# Filters_PWM60Hz.net
KiCad netlist of a schematic drawn in Altium Designer
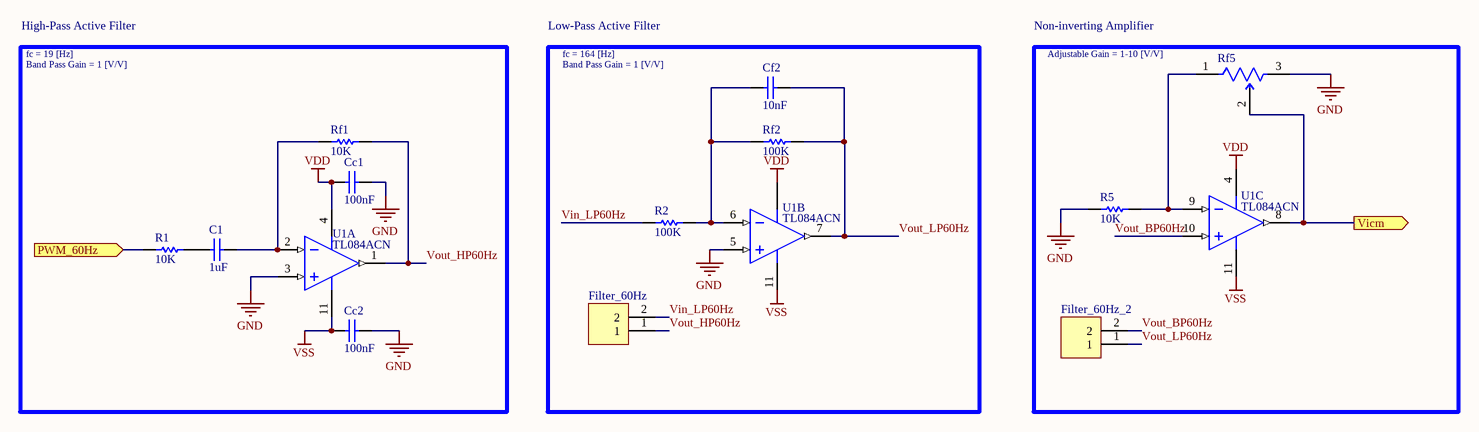
[diagram p0: Filters_PWM60Hz.SchDoc]

(export (version "E")
  (design (tool "Eeschema 10.0.6"))
  (components
    (comp (ref "C1")
      (value "1uF")
      (footprint "condensateur 0.1uf 100mil")
      (description "Capacitor")
      (fields (field (name "Comment") "Cap") (field (name "PUBLISHER") "Altium Limited"))
      (libsource (lib "signal-generator") (part "Cap"))
    )
    (comp (ref "Cc1")
      (value "100nF")
      (footprint "condensateur 0.1uf 100mil")
      (description "Capacitor")
      (fields (field (name "Comment") "Cap") (field (name "PUBLISHER") "Altium Limited"))
      (libsource (lib "signal-generator") (part "Cap"))
    )
    (comp (ref "Cc2")
      (value "100nF")
      (footprint "condensateur 0.1uf 100mil")
      (description "Capacitor")
      (fields (field (name "Comment") "Cap") (field (name "PUBLISHER") "Altium Limited"))
      (libsource (lib "signal-generator") (part "Cap"))
    )
    (comp (ref "Cf2")
      (value "10nF")
      (footprint "condensateur 0.1uf 100mil")
      (description "Capacitor")
      (fields (field (name "Comment") "Cap") (field (name "PUBLISHER") "Altium Limited"))
      (libsource (lib "signal-generator") (part "Cap"))
    )
    (comp (ref "Filter_60Hz")
      (value "Jumper")
      (footprint "Header 2P 100mil")
      (description "CONN HEADER VERT 3POS 2.54MM")
      (fields (field (name "PUBLISHER") "Altium Limited"))
      (libsource (lib "PCB_Alimentation_équipe1") (part "header 2 pin_UL"))
    )
    (comp (ref "Filter_60Hz_2")
      (value "Jumper")
      (footprint "Header 2P 100mil")
      (description "CONN HEADER VERT 3POS 2.54MM")
      (fields (field (name "PUBLISHER") "Altium Limited"))
      (libsource (lib "PCB_Alimentation_équipe1") (part "header 2 pin_UL"))
    )
    (comp (ref "R1")
      (value "10K")
      (footprint "Resistor_Axial 0.4")
      (description "Resistor")
      (fields (field (name "Comment") "Res1") (field (name "PUBLISHER") "Altium Limited"))
      (libsource (lib "signal-generator") (part "Res1"))
    )
    (comp (ref "R2")
      (value "100K")
      (footprint "Resistor_Axial 0.4")
      (description "Resistor")
      (fields (field (name "Comment") "Res1") (field (name "PUBLISHER") "Altium Limited"))
      (libsource (lib "signal-generator") (part "Res1"))
    )
    (comp (ref "R5")
      (value "10K")
      (footprint "Resistor_Axial 0.4")
      (description "Resistor")
      (fields (field (name "Comment") "Res1") (field (name "PUBLISHER") "Altium Limited"))
      (libsource (lib "signal-generator") (part "Res1"))
    )
    (comp (ref "Rf1")
      (value "10K")
      (footprint "Resistor_Axial 0.4")
      (description "Resistor")
      (fields (field (name "Comment") "Res1") (field (name "PUBLISHER") "Altium Limited"))
      (libsource (lib "signal-generator") (part "Res1"))
    )
    (comp (ref "Rf2")
      (value "100K")
      (footprint "Resistor_Axial 0.4")
      (description "Resistor")
      (fields (field (name "Comment") "Res1") (field (name "PUBLISHER") "Altium Limited"))
      (libsource (lib "signal-generator") (part "Res1"))
    )
    (comp (ref "Rf5")
      (value "67WR100KLF")
      (footprint "FP-67W-MFG")
      (description "TRIMMER 100K OHM 0.5W PC PIN TOP")
      (fields (field (name "TOLERANCE") "10%"))
      (libsource (lib "Altium Content Vault") (part "a77ee20e32664c43a3a1dd5392b6021"))
    )
    (comp (ref "U1")
      (value "TL084ACN")
      (footprint "N0014A")
      (description "JFET-Input Operational Amplifier, 7 to 36 V, 0 to 70 degC, 14-pin DIP (N14), Pb-Free (RoHS)")
      (fields (field (name "MANUFACTURER") "Texas Instruments"))
      (libsource (lib "Altium Content Vault") (part "TI-TLXX4X_MC3403-X14"))
    )
  )
  (nets
    (net (code "1") (name "/PWM_60Hz") (class "Default")
      (node (ref "R1") (pin "1") (pinfunction "1_1") (pintype "passive"))
    )
    (net (code "2") (name "/Vicm") (class "Default")
      (node (ref "Rf5") (pin "2") (pinfunction "2_2") (pintype "passive"))
      (node (ref "U1") (pin "8") (pinfunction "OUT3_8") (pintype "output"))
    )
    (net (code "3") (name "/Vin_LP60Hz") (class "Default")
      (node (ref "Filter_60Hz") (pin "2") (pinfunction "2_2") (pintype "passive"))
      (node (ref "R2") (pin "1") (pinfunction "1_1") (pintype "passive"))
    )
    (net (code "4") (name "/Vout_BP60Hz") (class "Default")
      (node (ref "Filter_60Hz_2") (pin "2") (pinfunction "2_2") (pintype "passive"))
      (node (ref "U1") (pin "10") (pinfunction "IN3+_10") (pintype "input"))
    )
    (net (code "5") (name "/Vout_HP60Hz") (class "Default")
      (node (ref "Filter_60Hz") (pin "1") (pinfunction "1_1") (pintype "passive"))
      (node (ref "Rf1") (pin "2") (pinfunction "2_2") (pintype "passive"))
      (node (ref "U1") (pin "1") (pinfunction "OUT1_1") (pintype "output"))
    )
    (net (code "6") (name "/Vout_LP60Hz") (class "Default")
      (node (ref "Cf2") (pin "2") (pinfunction "2_2") (pintype "passive"))
      (node (ref "Filter_60Hz_2") (pin "1") (pinfunction "1_1") (pintype "passive"))
      (node (ref "Rf2") (pin "2") (pinfunction "2_2") (pintype "passive"))
      (node (ref "U1") (pin "7") (pinfunction "OUT2_7") (pintype "output"))
    )
    (net (code "7") (name "GND") (class "Default")
      (node (ref "Cc1") (pin "2") (pinfunction "2_2") (pintype "passive"))
      (node (ref "Cc2") (pin "2") (pinfunction "2_2") (pintype "passive"))
      (node (ref "R5") (pin "1") (pinfunction "1_1") (pintype "passive"))
      (node (ref "Rf5") (pin "3") (pinfunction "3_3") (pintype "passive"))
      (node (ref "U1") (pin "3") (pinfunction "IN1+_3") (pintype "input"))
      (node (ref "U1") (pin "5") (pinfunction "IN2+_5") (pintype "input"))
    )
    (net (code "8") (name "Net-(C1-Pad1)") (class "Default")
      (node (ref "C1") (pin "1") (pinfunction "1_1") (pintype "passive"))
      (node (ref "R1") (pin "2") (pinfunction "2_2") (pintype "passive"))
    )
    (net (code "9") (name "Net-(U1A-IN1-)") (class "Default")
      (node (ref "C1") (pin "2") (pinfunction "2_2") (pintype "passive"))
      (node (ref "Rf1") (pin "1") (pinfunction "1_1") (pintype "passive"))
      (node (ref "U1") (pin "2") (pinfunction "IN1-_2") (pintype "input"))
    )
    (net (code "10") (name "Net-(U1B-IN2-)") (class "Default")
      (node (ref "Cf2") (pin "1") (pinfunction "1_1") (pintype "passive"))
      (node (ref "R2") (pin "2") (pinfunction "2_2") (pintype "passive"))
      (node (ref "Rf2") (pin "1") (pinfunction "1_1") (pintype "passive"))
      (node (ref "U1") (pin "6") (pinfunction "IN2-_6") (pintype "input"))
    )
    (net (code "11") (name "Net-(U1C-IN3-)") (class "Default")
      (node (ref "R5") (pin "2") (pinfunction "2_2") (pintype "passive"))
      (node (ref "Rf5") (pin "1") (pinfunction "1_1") (pintype "passive"))
      (node (ref "U1") (pin "9") (pinfunction "IN3-_9") (pintype "input"))
    )
    (net (code "12") (name "VDD") (class "Default")
      (node (ref "Cc1") (pin "1") (pinfunction "1_1") (pintype "passive"))
      (node (ref "U1") (pin "4") (pinfunction "VCC+_4") (pintype "power_in"))
    )
    (net (code "13") (name "VSS") (class "Default")
      (node (ref "Cc2") (pin "1") (pinfunction "1_1") (pintype "passive"))
      (node (ref "U1") (pin "11") (pinfunction "VCC-_11") (pintype "power_in"))
    )
  )
)
